# Hauptplatine.net
KiCad netlist of a schematic drawn in EAGLE
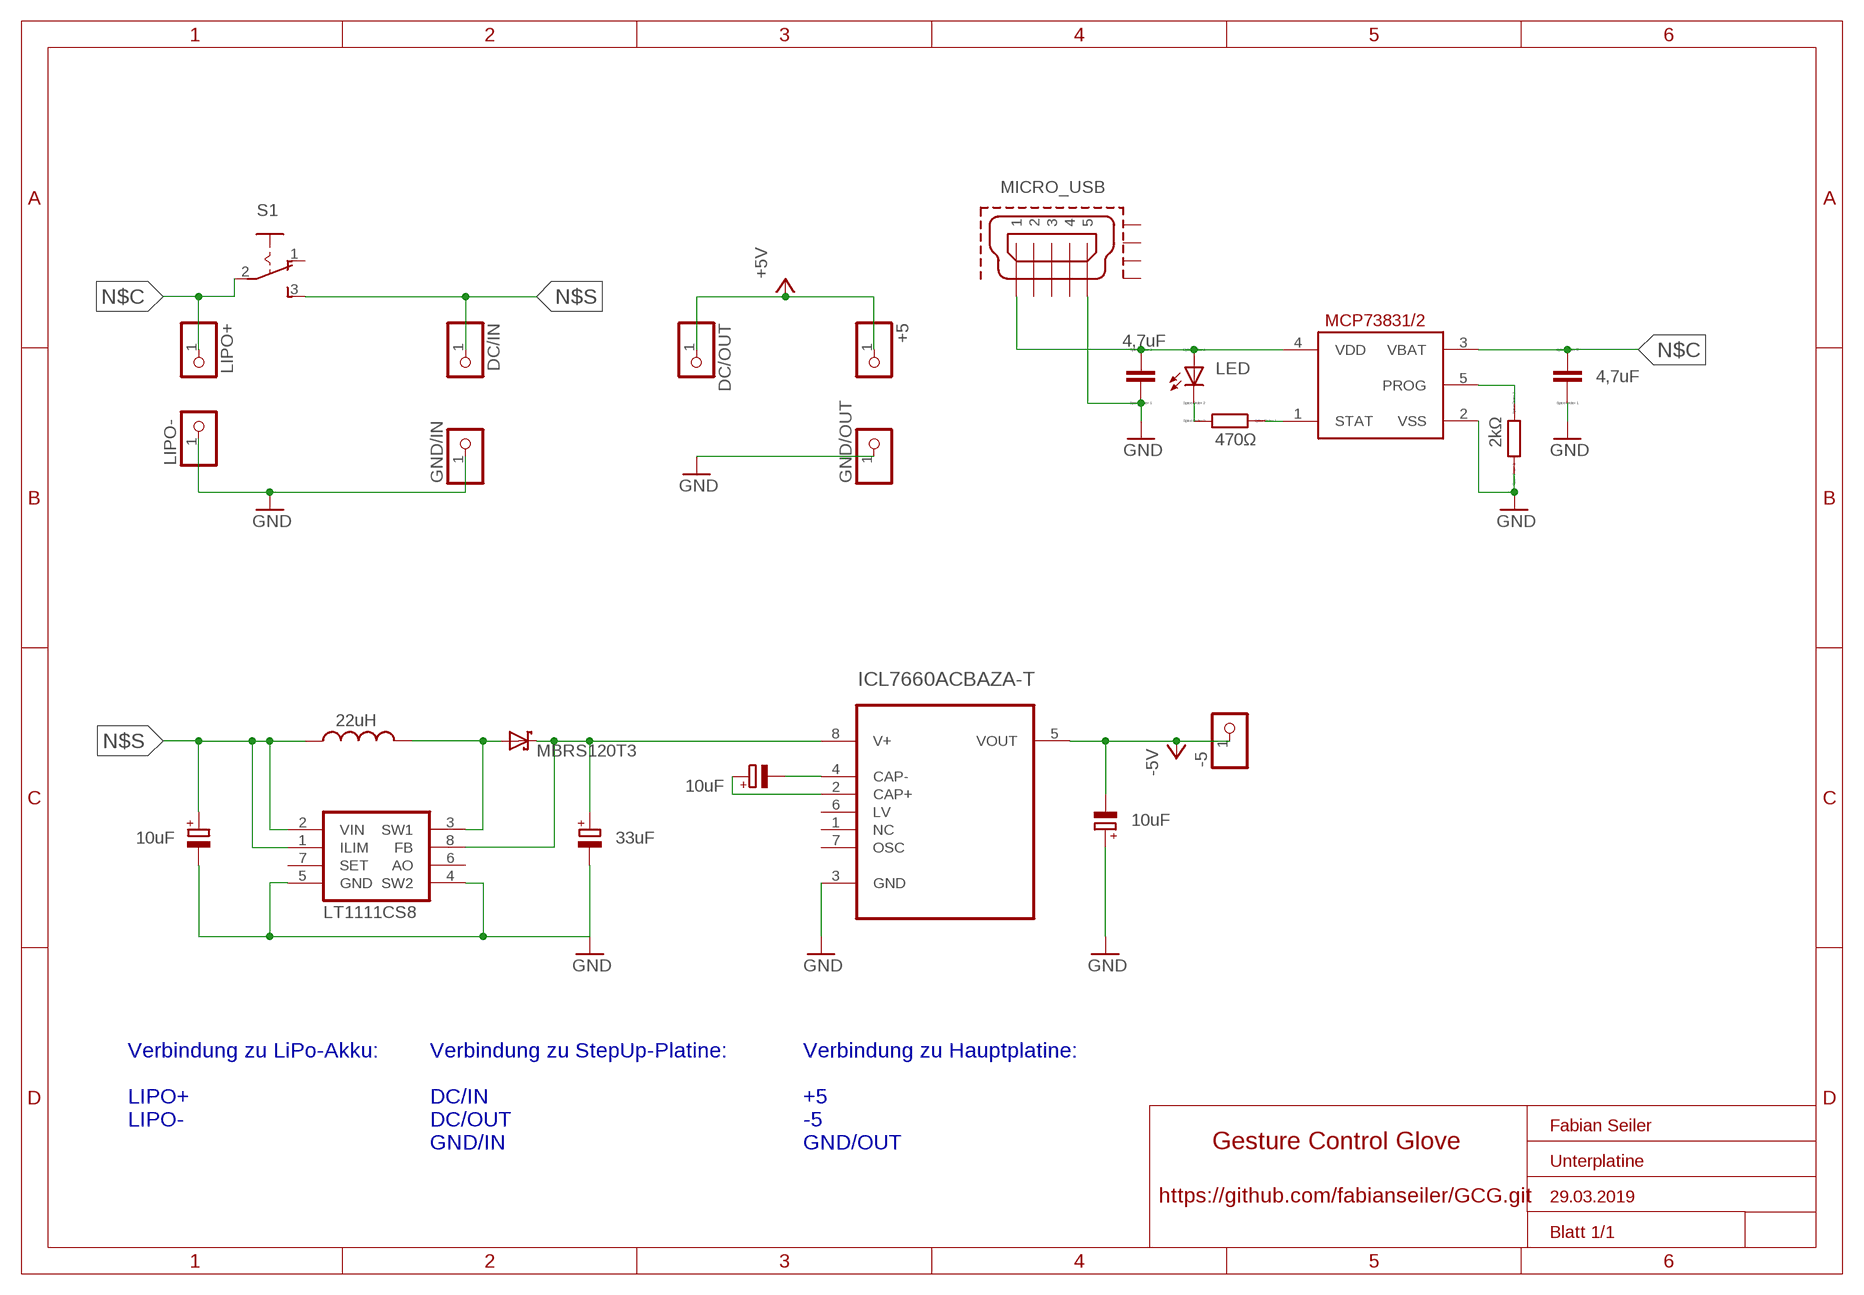
[diagram p0: schematic, sheet 1]

(export (version "E")
  (design (tool "Eeschema 10.0.6"))
  (components
    (comp (ref "+5")
      (value "PINHD-1X1CB")
      (footprint "eagle-import:1X01-CLEANBIG")
      (libsource (lib "eagle-import") (part "PINHD-1X1CB"))
    )
    (comp (ref "-5")
      (value "PINHD-1X1CB")
      (footprint "eagle-import:1X01-CLEANBIG")
      (libsource (lib "eagle-import") (part "PINHD-1X1CB"))
    )
    (comp (ref "CF3")
      (value "10uF")
      (footprint "eagle-import:153CLV-0505")
      (libsource (lib "eagle-import") (part "CPOL-EU153CLV-0505"))
    )
    (comp (ref "CF4")
      (value "33uF")
      (footprint "eagle-import:153CLV-0505")
      (libsource (lib "eagle-import") (part "CPOL-EU153CLV-0505"))
    )
    (comp (ref "CF5")
      (value "10uF")
      (footprint "eagle-import:153CLV-0505")
      (libsource (lib "eagle-import") (part "CPOL-EU153CLV-0505"))
    )
    (comp (ref "CF6")
      (value "10uF")
      (footprint "eagle-import:153CLV-0505")
      (libsource (lib "eagle-import") (part "CPOL-EU153CLV-0505"))
    )
    (comp (ref "C_L1")
      (value "4,7uF")
      (footprint "eagle-import:C0402")
      (libsource (lib "eagle-import") (part "C-EUC0402"))
    )
    (comp (ref "C_L2")
      (value "4,7uF")
      (footprint "eagle-import:C0402")
      (libsource (lib "eagle-import") (part "C-EUC0402"))
    )
    (comp (ref "DC/IN")
      (value "PINHD-1X1CB")
      (footprint "eagle-import:1X01-CLEANBIG")
      (libsource (lib "eagle-import") (part "PINHD-1X1CB"))
    )
    (comp (ref "DC/OUT")
      (value "PINHD-1X1CB")
      (footprint "eagle-import:1X01-CLEANBIG")
      (libsource (lib "eagle-import") (part "PINHD-1X1CB"))
    )
    (comp (ref "D_PS1")
      (value "MBRS120T3")
      (footprint "eagle-import:DO214AA")
      (libsource (lib "eagle-import") (part "MBRS120T3"))
    )
    (comp (ref "GND/IN")
      (value "PINHD-1X1CB")
      (footprint "eagle-import:1X01-CLEANBIG")
      (libsource (lib "eagle-import") (part "PINHD-1X1CB"))
    )
    (comp (ref "GND/OUT")
      (value "PINHD-1X1CB")
      (footprint "eagle-import:1X01-CLEANBIG")
      (libsource (lib "eagle-import") (part "PINHD-1X1CB"))
    )
    (comp (ref "IC1")
      (value "MCP73831/OT")
      (footprint "eagle-import:SOT23-5L")
      (libsource (lib "eagle-import") (part "MCP73831/OT"))
    )
    (comp (ref "IC3")
      (value "LT1111CS8")
      (footprint "eagle-import:SO08")
      (libsource (lib "eagle-import") (part "LT1111S8C"))
    )
    (comp (ref "L-242408FPS1")
      (value "22uH")
      (footprint "eagle-import:L2012C")
      (libsource (lib "eagle-import") (part "L-USL2012C"))
    )
    (comp (ref "LED")
      (value "LED_ESML0603")
      (footprint "eagle-import:LED_SML0603")
      (libsource (lib "eagle-import") (part "LED_ESML0603"))
    )
    (comp (ref "LIPO+")
      (value "PINHD-1X1CB")
      (footprint "eagle-import:1X01-CLEANBIG")
      (libsource (lib "eagle-import") (part "PINHD-1X1CB"))
    )
    (comp (ref "LIPO-")
      (value "PINHD-1X1CB")
      (footprint "eagle-import:1X01-CLEANBIG")
      (libsource (lib "eagle-import") (part "PINHD-1X1CB"))
    )
    (comp (ref "MICRO_USB")
      (value "MICRO-USB-RECEPTACLE47589-0001")
      (footprint "eagle-import:47589-0001")
      (libsource (lib "eagle-import") (part "MICRO-USB-RECEPTACLE47589-0001"))
    )
    (comp (ref "R_BMC")
      (value "470Ω")
      (footprint "eagle-import:R0402")
      (libsource (lib "eagle-import") (part "R-EU_R0402"))
    )
    (comp (ref "R_BMC2")
      (value "2kΩ")
      (footprint "eagle-import:R0402")
      (libsource (lib "eagle-import") (part "R-EU_R0402"))
    )
    (comp (ref "S1")
      (value "255SB")
      (footprint "eagle-import:255SB")
      (libsource (lib "eagle-import") (part "255SB"))
    )
    (comp (ref "U1")
      (value "ICL7660ACBAZA-T")
      (footprint "eagle-import:SOIC127P600X175-8N")
      (fields
        (field (name "DIGI-KEY_PART_NUMBER") "ICL7660ACBAZA-TCT-ND")
        (field (name "MF") "Renesas Electronics")
      )
      (libsource (lib "eagle-import") (part "ICL7660ACBAZA-T"))
    )
  )
  (nets
    (net (code "1") (name "+5V") (class "Default")
      (node (ref "+5") (pin "1") (pinfunction "1_1") (pintype "passive"))
      (node (ref "DC/OUT") (pin "1") (pinfunction "1_1") (pintype "passive"))
    )
    (net (code "2") (name "-5V") (class "Default")
      (node (ref "-5") (pin "1") (pinfunction "1_1") (pintype "passive"))
      (node (ref "CF6") (pin "-") (pinfunction "-_-") (pintype "passive"))
      (node (ref "U1") (pin "5") (pinfunction "VOUT_5") (pintype "output"))
    )
    (net (code "3") (name "GND") (class "Default")
      (node (ref "CF3") (pin "-") (pinfunction "-_-") (pintype "passive"))
      (node (ref "CF4") (pin "-") (pinfunction "-_-") (pintype "passive"))
      (node (ref "CF6") (pin "+") (pinfunction "+_+") (pintype "passive"))
      (node (ref "C_L1") (pin "1") (pinfunction "1_1") (pintype "passive"))
      (node (ref "C_L2") (pin "1") (pinfunction "1_1") (pintype "passive"))
      (node (ref "GND/IN") (pin "1") (pinfunction "1_1") (pintype "passive"))
      (node (ref "GND/OUT") (pin "1") (pinfunction "1_1") (pintype "passive"))
      (node (ref "IC1") (pin "2") (pinfunction "VSS_2") (pintype "power_in"))
      (node (ref "IC3") (pin "4") (pinfunction "SW2_4") (pintype "passive"))
      (node (ref "IC3") (pin "5") (pinfunction "GND_5") (pintype "power_in"))
      (node (ref "LIPO-") (pin "1") (pinfunction "1_1") (pintype "passive"))
      (node (ref "MICRO_USB") (pin "5") (pinfunction "5_5") (pintype "input"))
      (node (ref "R_BMC2") (pin "1") (pinfunction "1_1") (pintype "passive"))
      (node (ref "U1") (pin "3") (pinfunction "GND_3") (pintype "passive"))
    )
    (net (code "4") (name "N$C") (class "Default")
      (node (ref "C_L2") (pin "2") (pinfunction "2_2") (pintype "passive"))
      (node (ref "IC1") (pin "3") (pinfunction "VBAT_3") (pintype "bidirectional"))
      (node (ref "LIPO+") (pin "1") (pinfunction "1_1") (pintype "passive"))
      (node (ref "S1") (pin "2") (pinfunction "P_2") (pintype "passive"))
    )
    (net (code "5") (name "N$S") (class "Default")
      (node (ref "CF3") (pin "+") (pinfunction "+_+") (pintype "passive"))
      (node (ref "DC/IN") (pin "1") (pinfunction "1_1") (pintype "passive"))
      (node (ref "IC3") (pin "1") (pinfunction "ILIM_1") (pintype "input"))
      (node (ref "IC3") (pin "2") (pinfunction "VIN_2") (pintype "input"))
      (node (ref "L-242408FPS1") (pin "1") (pinfunction "1_1") (pintype "passive"))
      (node (ref "S1") (pin "3") (pinfunction "S_3") (pintype "passive"))
    )
    (net (code "6") (name "Net-(IC1-PROG)") (class "Default")
      (node (ref "IC1") (pin "5") (pinfunction "PROG_5") (pintype "input"))
      (node (ref "R_BMC2") (pin "2") (pinfunction "2_2") (pintype "passive"))
    )
    (net (code "7") (name "Net-(IC1-STAT)") (class "Default")
      (node (ref "IC1") (pin "1") (pinfunction "STAT_1") (pintype "output"))
      (node (ref "R_BMC") (pin "1") (pinfunction "1_1") (pintype "passive"))
    )
    (net (code "8") (name "Net-(IC1-VDD)") (class "Default")
      (node (ref "C_L1") (pin "2") (pinfunction "2_2") (pintype "passive"))
      (node (ref "IC1") (pin "4") (pinfunction "VDD_4") (pintype "power_in"))
      (node (ref "LED") (pin "A") (pinfunction "A_A") (pintype "passive"))
      (node (ref "MICRO_USB") (pin "1") (pinfunction "1_1") (pintype "input"))
    )
    (net (code "9") (name "Net-(IC3-FB)") (class "Default")
      (node (ref "CF4") (pin "+") (pinfunction "+_+") (pintype "passive"))
      (node (ref "D_PS1") (pin "C") (pinfunction "C_C") (pintype "passive"))
      (node (ref "IC3") (pin "8") (pinfunction "FB_8") (pintype "input"))
      (node (ref "U1") (pin "8") (pinfunction "V+_8") (pintype "power_in"))
    )
    (net (code "10") (name "Net-(IC3-SW1)") (class "Default")
      (node (ref "D_PS1") (pin "A") (pinfunction "A_A") (pintype "passive"))
      (node (ref "IC3") (pin "3") (pinfunction "SW1_3") (pintype "passive"))
      (node (ref "L-242408FPS1") (pin "2") (pinfunction "2_2") (pintype "passive"))
    )
    (net (code "11") (name "Net-(LED-PadC)") (class "Default")
      (node (ref "LED") (pin "C") (pinfunction "C_C") (pintype "passive"))
      (node (ref "R_BMC") (pin "2") (pinfunction "2_2") (pintype "passive"))
    )
    (net (code "12") (name "Net-(U1-CAP+)") (class "Default")
      (node (ref "CF5") (pin "+") (pinfunction "+_+") (pintype "passive"))
      (node (ref "U1") (pin "2") (pinfunction "CAP+_2") (pintype "passive"))
    )
    (net (code "13") (name "Net-(U1-CAP-)") (class "Default")
      (node (ref "CF5") (pin "-") (pinfunction "-_-") (pintype "passive"))
      (node (ref "U1") (pin "4") (pinfunction "CAP-_4") (pintype "passive"))
    )
    (net (code "14") (name "unconnected-(IC3-AO-Pad6)") (class "Default")
      (node (ref "IC3") (pin "6") (pinfunction "AO_6") (pintype "open_collector"))
    )
    (net (code "15") (name "unconnected-(IC3-SET-Pad7)") (class "Default")
      (node (ref "IC3") (pin "7") (pinfunction "SET_7") (pintype "input"))
    )
    (net (code "16") (name "unconnected-(MICRO_USB-GND1-PadCASING1)") (class "Default")
      (node (ref "MICRO_USB") (pin "CASING1") (pinfunction "GND1_CASING1") (pintype "bidirectional"))
    )
    (net (code "17") (name "unconnected-(MICRO_USB-GND2-PadCASING2)") (class "Default")
      (node (ref "MICRO_USB") (pin "CASING2") (pinfunction "GND2_CASING2") (pintype "bidirectional"))
    )
    (net (code "18") (name "unconnected-(MICRO_USB-GND3-PadCASING3)") (class "Default")
      (node (ref "MICRO_USB") (pin "CASING3") (pinfunction "GND3_CASING3") (pintype "bidirectional"))
    )
    (net (code "19") (name "unconnected-(MICRO_USB-GND4-PadCASING4)") (class "Default")
      (node (ref "MICRO_USB") (pin "CASING4") (pinfunction "GND4_CASING4") (pintype "bidirectional"))
    )
    (net (code "20") (name "unconnected-(MICRO_USB-Pad2)") (class "Default")
      (node (ref "MICRO_USB") (pin "2") (pinfunction "2_2") (pintype "input"))
    )
    (net (code "21") (name "unconnected-(MICRO_USB-Pad3)") (class "Default")
      (node (ref "MICRO_USB") (pin "3") (pinfunction "3_3") (pintype "input"))
    )
    (net (code "22") (name "unconnected-(MICRO_USB-Pad4)") (class "Default")
      (node (ref "MICRO_USB") (pin "4") (pinfunction "4_4") (pintype "input"))
    )
    (net (code "23") (name "unconnected-(S1-O-Pad1)") (class "Default")
      (node (ref "S1") (pin "1") (pinfunction "O_1") (pintype "passive"))
    )
    (net (code "24") (name "unconnected-(U1-LV-Pad6)") (class "Default")
      (node (ref "U1") (pin "6") (pinfunction "LV_6") (pintype "input"))
    )
    (net (code "25") (name "unconnected-(U1-NC-Pad1)") (class "Default")
      (node (ref "U1") (pin "1") (pinfunction "NC_1") (pintype "no_connect"))
    )
    (net (code "26") (name "unconnected-(U1-OSC-Pad7)") (class "Default")
      (node (ref "U1") (pin "7") (pinfunction "OSC_7") (pintype "input"))
    )
  )
)
